# board6.net
KiCad netlist of a schematic drawn in Altium Designer
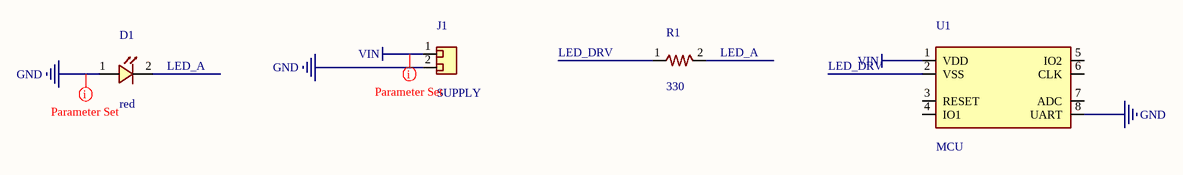
[diagram p0: board6.SchDoc]

(export (version "E")
  (design (tool "Eeschema 10.0.6"))
  (components
    (comp (ref "D1")
      (value "red")
      (footprint "board6:LED0603_Kingbright_APT1608SURCK")
      (libsource (lib "board6") (part "LED"))
    )
    (comp (ref "J1")
      (value "SUPPLY")
      (footprint "board6:Header_1x2_P2.54")
      (libsource (lib "board6") (part "Connector_2"))
    )
    (comp (ref "R1")
      (value "330")
      (footprint "board6:Chip_0603")
      (libsource (lib "board6") (part "Resistor"))
    )
    (comp (ref "U1")
      (value "MCU")
      (footprint "board6:DIP8_Microchip_P")
      (libsource (lib "board6") (part "Microcontroller"))
    )
  )
  (nets
    (net (code "1") (name "/LED_A") (class "Default")
      (node (ref "D1") (pin "2") (pinfunction "K_2") (pintype "passive"))
      (node (ref "R1") (pin "2") (pinfunction "B_2") (pintype "passive"))
    )
    (net (code "2") (name "/LED_DRV") (class "Default")
      (node (ref "R1") (pin "1") (pinfunction "A_1") (pintype "passive"))
      (node (ref "U1") (pin "2") (pinfunction "VSS_2") (pintype "passive"))
    )
    (net (code "3") (name "GND") (class "Default")
      (node (ref "D1") (pin "1") (pinfunction "A_1") (pintype "passive"))
      (node (ref "J1") (pin "2") (pinfunction "Passive_2") (pintype "passive"))
      (node (ref "U1") (pin "8") (pinfunction "UART_8") (pintype "passive"))
    )
    (net (code "4") (name "VIN") (class "Default")
      (node (ref "J1") (pin "1") (pinfunction "Passive_1") (pintype "passive"))
      (node (ref "U1") (pin "1") (pinfunction "VDD_1") (pintype "passive"))
    )
    (net (code "5") (name "unconnected-(U1-ADC-Pad7)") (class "Default")
      (node (ref "U1") (pin "7") (pinfunction "ADC_7") (pintype "passive"))
    )
    (net (code "6") (name "unconnected-(U1-CLK-Pad6)") (class "Default")
      (node (ref "U1") (pin "6") (pinfunction "CLK_6") (pintype "passive"))
    )
    (net (code "7") (name "unconnected-(U1-IO1-Pad4)") (class "Default")
      (node (ref "U1") (pin "4") (pinfunction "IO1_4") (pintype "passive"))
    )
    (net (code "8") (name "unconnected-(U1-IO2-Pad5)") (class "Default")
      (node (ref "U1") (pin "5") (pinfunction "IO2_5") (pintype "passive"))
    )
    (net (code "9") (name "unconnected-(U1-RESET-Pad3)") (class "Default")
      (node (ref "U1") (pin "3") (pinfunction "RESET_3") (pintype "passive"))
    )
  )
)
